# Vsense_0-69_3V.net
KiCad netlist of a schematic drawn in Altium Designer
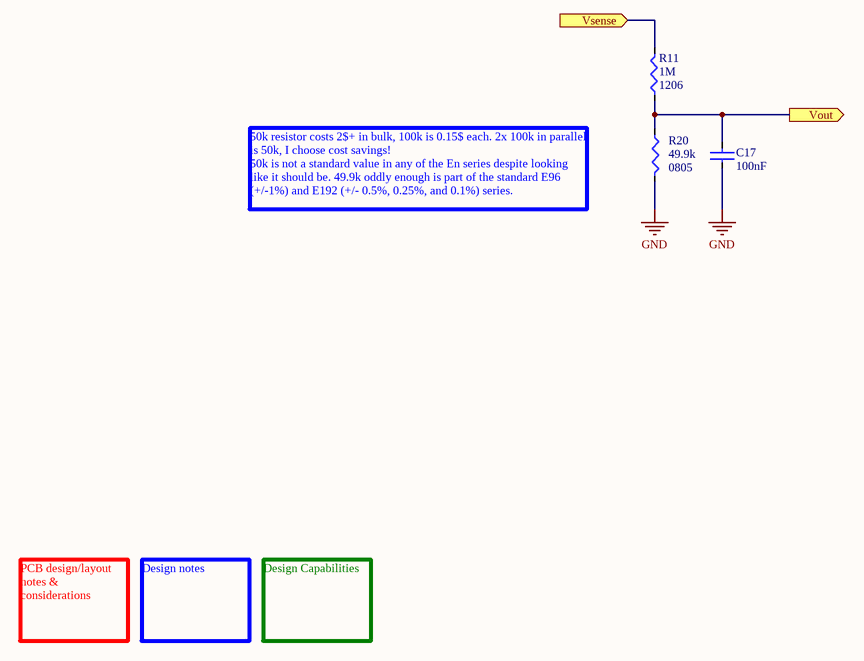
[diagram p0: Vsense 0-69.3V.SchDoc]

(export (version "E")
  (design (tool "Eeschema 10.0.6"))
  (components
    (comp (ref "C17")
      (value "100nF 0603 50V")
      (footprint "C0603 - Ceramic")
      (fields
        (field (name "MANUFACTURER") "Samsung Electro-Mechanics America, Inc")
        (field (name "MANUFACTURER PART NUMBER") "CL10B104KB8SFNC")
        (field (name "TOLERANCE") "±10%")
        (field (name "CAPACITANCE") "100nF")
      )
      (libsource (lib "Personal Library") (part "100nF 0603 50V"))
    )
    (comp (ref "R11")
      (value "1M 1206 1%")
      (footprint "R1210")
      (description "Resistor")
      (fields
        (field (name "MANUFACTURER") "Yageo")
        (field (name "MANUFACTURER PART NUMBER") "RV1206FR-071ML")
        (field (name "RESISTANCE (OHMS)") "1M")
        (field (name "SUPPLIER DEVICE PACKAGE") "1206")
      )
      (libsource (lib "Local Library") (part "1M 1206 1%"))
    )
    (comp (ref "R20")
      (value "Template - Resistor")
      (footprint "R0805")
      (fields
        (field (name "MANUFACTURER") "Yageo")
        (field (name "MANUFACTURER PART NUMBER") "RC0805FR-0749K9L")
        (field (name "RESISTANCE (OHMS)") "49.9k")
        (field (name "TOLERANCE") "±1%")
        (field (name "SUPPLIER DEVICE PACKAGE") "0805")
      )
      (libsource (lib "Personal Library") (part "Template - Resistor"))
    )
  )
  (nets
    (net (code "1") (name "/Vout") (class "Default")
      (node (ref "C17") (pin "1") (pinfunction "1_1") (pintype "passive"))
      (node (ref "R11") (pin "2") (pinfunction "2_2") (pintype "passive"))
      (node (ref "R20") (pin "2") (pinfunction "2_2") (pintype "passive"))
    )
    (net (code "2") (name "/Vsense") (class "Default")
      (node (ref "R11") (pin "1") (pinfunction "1_1") (pintype "passive"))
    )
    (net (code "3") (name "GND") (class "Default")
      (node (ref "C17") (pin "2") (pinfunction "2_2") (pintype "passive"))
      (node (ref "R20") (pin "1") (pinfunction "1_1") (pintype "passive"))
    )
  )
)
